# odpojovac.net
KiCad netlist of a schematic drawn in EAGLE
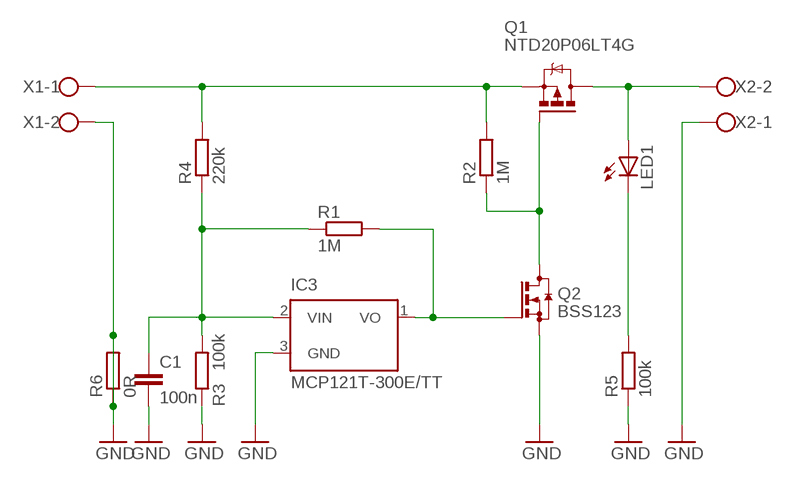
[diagram p0: schematic, sheet 1]

(export (version "E")
  (design (tool "Eeschema 10.0.6"))
  (components
    (comp (ref "C1")
      (value "100n")
      (footprint "eagle-import:C0805K")
      (libsource (lib "eagle-import") (part "C-EUC0805K"))
    )
    (comp (ref "IC3")
      (value "MCP121T-300E/TT")
      (footprint "eagle-import:SOT23")
      (libsource (lib "eagle-import") (part "MCP102"))
    )
    (comp (ref "LED1")
      (value "LEDCHIPLED_0805")
      (footprint "eagle-import:CHIPLED_0805")
      (libsource (lib "eagle-import") (part "LEDCHIPLED_0805"))
    )
    (comp (ref "Q1")
      (value "NTD20P06LT4G")
      (footprint "eagle-import:D-PAK_TO252AA")
      (libsource (lib "eagle-import") (part "IRF?5305R"))
    )
    (comp (ref "Q2")
      (value "BSS123")
      (footprint "eagle-import:SOT23")
      (libsource (lib "eagle-import") (part "BSS123"))
    )
    (comp (ref "R1")
      (value "1M")
      (footprint "eagle-import:R0805")
      (libsource (lib "eagle-import") (part "R-EU_R0805"))
    )
    (comp (ref "R2")
      (value "1M")
      (footprint "eagle-import:R0805")
      (libsource (lib "eagle-import") (part "R-EU_R0805"))
    )
    (comp (ref "R3")
      (value "100k")
      (footprint "eagle-import:R0805")
      (libsource (lib "eagle-import") (part "R-EU_R0805"))
    )
    (comp (ref "R4")
      (value "220k")
      (footprint "eagle-import:R0805")
      (libsource (lib "eagle-import") (part "R-EU_R0805"))
    )
    (comp (ref "R5")
      (value "100k")
      (footprint "eagle-import:R0805")
      (libsource (lib "eagle-import") (part "R-EU_R0805"))
    )
    (comp (ref "R6")
      (value "0R")
      (footprint "eagle-import:R1206")
      (libsource (lib "eagle-import") (part "R-EU_R1206"))
    )
    (comp (ref "X1")
      (value "W237-102")
      (footprint "eagle-import:W237-102")
      (libsource (lib "eagle-import") (part "W237-102"))
    )
    (comp (ref "X2")
      (value "W237-102")
      (footprint "eagle-import:W237-102")
      (libsource (lib "eagle-import") (part "W237-102"))
    )
  )
  (nets
    (net (code "1") (name "GND") (class "Default")
      (node (ref "C1") (pin "2") (pinfunction "2_2") (pintype "passive"))
      (node (ref "IC3") (pin "3") (pinfunction "GND_3") (pintype "passive"))
      (node (ref "Q2") (pin "2") (pinfunction "S_2") (pintype "passive"))
      (node (ref "R3") (pin "1") (pinfunction "1_1") (pintype "passive"))
      (node (ref "R5") (pin "1") (pinfunction "1_1") (pintype "passive"))
      (node (ref "R6") (pin "1") (pinfunction "1_1") (pintype "passive"))
      (node (ref "R6") (pin "2") (pinfunction "2_2") (pintype "passive"))
      (node (ref "X1") (pin "2") (pinfunction "KL_2") (pintype "passive"))
      (node (ref "X2") (pin "1") (pinfunction "KL_1") (pintype "passive"))
    )
    (net (code "2") (name "Net-(IC3-VIN)") (class "Default")
      (node (ref "C1") (pin "1") (pinfunction "1_1") (pintype "passive"))
      (node (ref "IC3") (pin "2") (pinfunction "VIN_2") (pintype "input"))
      (node (ref "R1") (pin "1") (pinfunction "1_1") (pintype "passive"))
      (node (ref "R3") (pin "2") (pinfunction "2_2") (pintype "passive"))
      (node (ref "R4") (pin "1") (pinfunction "1_1") (pintype "passive"))
    )
    (net (code "3") (name "Net-(IC3-VO)") (class "Default")
      (node (ref "IC3") (pin "1") (pinfunction "VO_1") (pintype "output"))
      (node (ref "Q2") (pin "1") (pinfunction "G_1") (pintype "passive"))
      (node (ref "R1") (pin "2") (pinfunction "2_2") (pintype "passive"))
    )
    (net (code "4") (name "Net-(LED1-PadC)") (class "Default")
      (node (ref "LED1") (pin "C") (pinfunction "C_C") (pintype "passive"))
      (node (ref "R5") (pin "2") (pinfunction "2_2") (pintype "passive"))
    )
    (net (code "5") (name "Net-(Q1-D)") (class "Default")
      (node (ref "LED1") (pin "A") (pinfunction "A_A") (pintype "passive"))
      (node (ref "Q1") (pin "4") (pinfunction "D_4") (pintype "passive"))
      (node (ref "X2") (pin "2") (pinfunction "KL_2") (pintype "passive"))
    )
    (net (code "6") (name "Net-(Q1-G)") (class "Default")
      (node (ref "Q1") (pin "1") (pinfunction "G_1") (pintype "passive"))
      (node (ref "Q2") (pin "3") (pinfunction "D_3") (pintype "passive"))
      (node (ref "R2") (pin "1") (pinfunction "1_1") (pintype "passive"))
    )
    (net (code "7") (name "Net-(Q1-S)") (class "Default")
      (node (ref "Q1") (pin "3") (pinfunction "S_3") (pintype "passive"))
      (node (ref "R2") (pin "2") (pinfunction "2_2") (pintype "passive"))
      (node (ref "R4") (pin "2") (pinfunction "2_2") (pintype "passive"))
      (node (ref "X1") (pin "1") (pinfunction "KL_1") (pintype "passive"))
    )
  )
)
